# Pico_LED_Matrix_A1.net
KiCad netlist of a schematic drawn in EAGLE
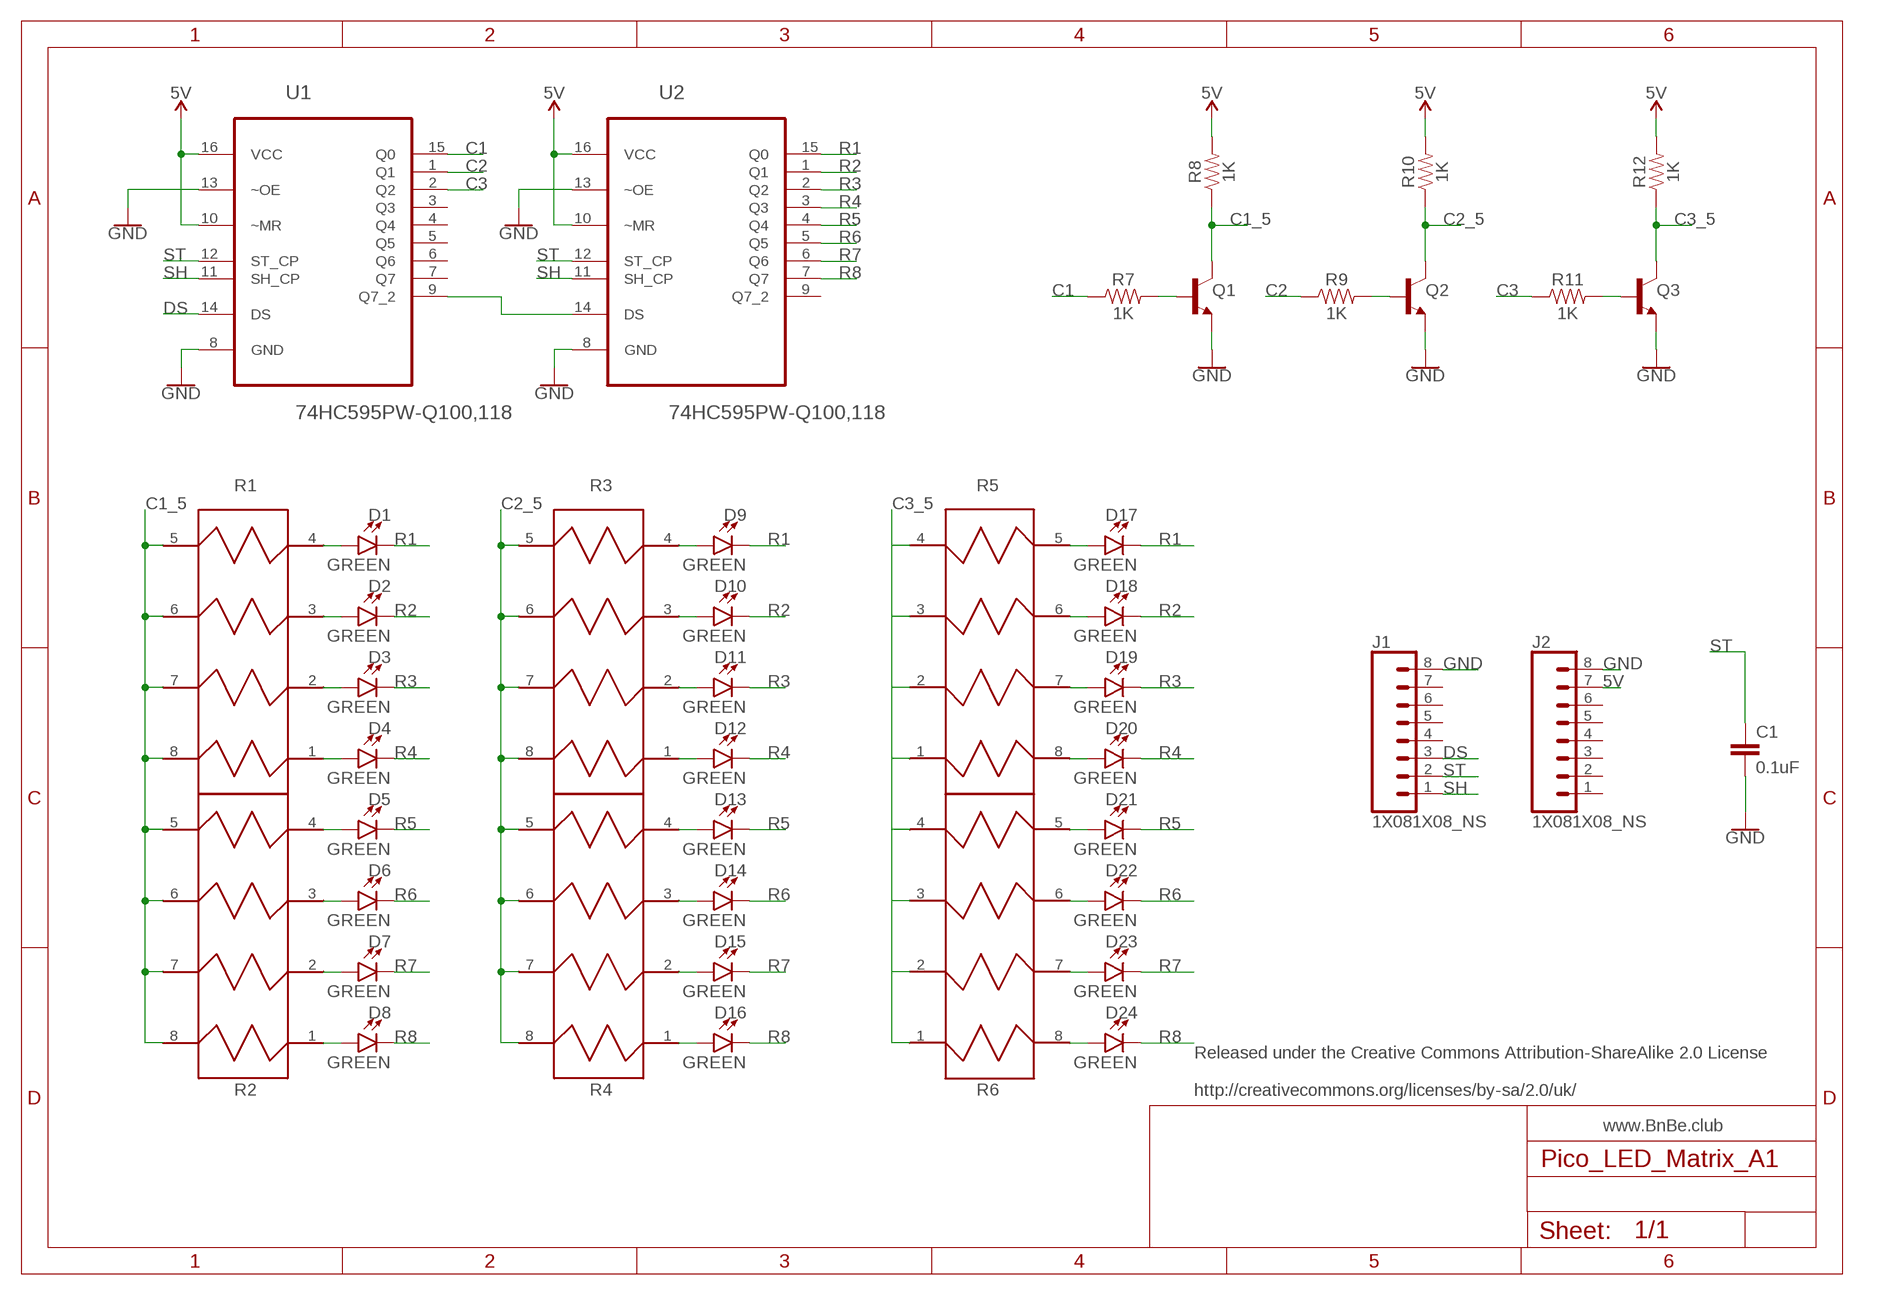
[diagram p0: schematic, sheet 1]

(export (version "E")
  (design (tool "Eeschema 10.0.6"))
  (components
    (comp (ref "C1")
      (value "0.1uF")
      (footprint "eagle-import:0402")
      (libsource (lib "eagle-import") (part "0.1UF-0402-16V-10%"))
    )
    (comp (ref "D1")
      (value "GREEN")
      (footprint "eagle-import:LED-0603")
      (libsource (lib "eagle-import") (part "LED-GREEN0603"))
    )
    (comp (ref "D2")
      (value "GREEN")
      (footprint "eagle-import:LED-0603")
      (libsource (lib "eagle-import") (part "LED-GREEN0603"))
    )
    (comp (ref "D3")
      (value "GREEN")
      (footprint "eagle-import:LED-0603")
      (libsource (lib "eagle-import") (part "LED-GREEN0603"))
    )
    (comp (ref "D4")
      (value "GREEN")
      (footprint "eagle-import:LED-0603")
      (libsource (lib "eagle-import") (part "LED-GREEN0603"))
    )
    (comp (ref "D5")
      (value "GREEN")
      (footprint "eagle-import:LED-0603")
      (libsource (lib "eagle-import") (part "LED-GREEN0603"))
    )
    (comp (ref "D6")
      (value "GREEN")
      (footprint "eagle-import:LED-0603")
      (libsource (lib "eagle-import") (part "LED-GREEN0603"))
    )
    (comp (ref "D7")
      (value "GREEN")
      (footprint "eagle-import:LED-0603")
      (libsource (lib "eagle-import") (part "LED-GREEN0603"))
    )
    (comp (ref "D8")
      (value "GREEN")
      (footprint "eagle-import:LED-0603")
      (libsource (lib "eagle-import") (part "LED-GREEN0603"))
    )
    (comp (ref "D9")
      (value "GREEN")
      (footprint "eagle-import:LED-0603")
      (libsource (lib "eagle-import") (part "LED-GREEN0603"))
    )
    (comp (ref "D10")
      (value "GREEN")
      (footprint "eagle-import:LED-0603")
      (libsource (lib "eagle-import") (part "LED-GREEN0603"))
    )
    (comp (ref "D11")
      (value "GREEN")
      (footprint "eagle-import:LED-0603")
      (libsource (lib "eagle-import") (part "LED-GREEN0603"))
    )
    (comp (ref "D12")
      (value "GREEN")
      (footprint "eagle-import:LED-0603")
      (libsource (lib "eagle-import") (part "LED-GREEN0603"))
    )
    (comp (ref "D13")
      (value "GREEN")
      (footprint "eagle-import:LED-0603")
      (libsource (lib "eagle-import") (part "LED-GREEN0603"))
    )
    (comp (ref "D14")
      (value "GREEN")
      (footprint "eagle-import:LED-0603")
      (libsource (lib "eagle-import") (part "LED-GREEN0603"))
    )
    (comp (ref "D15")
      (value "GREEN")
      (footprint "eagle-import:LED-0603")
      (libsource (lib "eagle-import") (part "LED-GREEN0603"))
    )
    (comp (ref "D16")
      (value "GREEN")
      (footprint "eagle-import:LED-0603")
      (libsource (lib "eagle-import") (part "LED-GREEN0603"))
    )
    (comp (ref "D17")
      (value "GREEN")
      (footprint "eagle-import:LED-0603")
      (libsource (lib "eagle-import") (part "LED-GREEN0603"))
    )
    (comp (ref "D18")
      (value "GREEN")
      (footprint "eagle-import:LED-0603")
      (libsource (lib "eagle-import") (part "LED-GREEN0603"))
    )
    (comp (ref "D19")
      (value "GREEN")
      (footprint "eagle-import:LED-0603")
      (libsource (lib "eagle-import") (part "LED-GREEN0603"))
    )
    (comp (ref "D20")
      (value "GREEN")
      (footprint "eagle-import:LED-0603")
      (libsource (lib "eagle-import") (part "LED-GREEN0603"))
    )
    (comp (ref "D21")
      (value "GREEN")
      (footprint "eagle-import:LED-0603")
      (libsource (lib "eagle-import") (part "LED-GREEN0603"))
    )
    (comp (ref "D22")
      (value "GREEN")
      (footprint "eagle-import:LED-0603")
      (libsource (lib "eagle-import") (part "LED-GREEN0603"))
    )
    (comp (ref "D23")
      (value "GREEN")
      (footprint "eagle-import:LED-0603")
      (libsource (lib "eagle-import") (part "LED-GREEN0603"))
    )
    (comp (ref "D24")
      (value "GREEN")
      (footprint "eagle-import:LED-0603")
      (libsource (lib "eagle-import") (part "LED-GREEN0603"))
    )
    (comp (ref "J1")
      (value "1X081X08_NS")
      (footprint "eagle-import:1X08_NS")
      (libsource (lib "eagle-import") (part "1X081X08_NS"))
    )
    (comp (ref "J2")
      (value "1X081X08_NS")
      (footprint "eagle-import:1X08_NS")
      (libsource (lib "eagle-import") (part "1X081X08_NS"))
    )
    (comp (ref "Q1")
      (value "TRANS_NPN-MMBT2222AL")
      (footprint "eagle-import:SOT23-3")
      (libsource (lib "eagle-import") (part "TRANS_NPN-MMBT2222AL"))
    )
    (comp (ref "Q2")
      (value "TRANS_NPN-MMBT2222AL")
      (footprint "eagle-import:SOT23-3")
      (libsource (lib "eagle-import") (part "TRANS_NPN-MMBT2222AL"))
    )
    (comp (ref "Q3")
      (value "TRANS_NPN-MMBT2222AL")
      (footprint "eagle-import:SOT23-3")
      (libsource (lib "eagle-import") (part "TRANS_NPN-MMBT2222AL"))
    )
    (comp (ref "R1")
      (value "EXBN8V220JX")
      (footprint "eagle-import:RESCAV50P200X100X55-8N")
      (fields (field (name "MF") "Panasonic Electronic") (field (name "MP") "EXB-N8V220JX"))
      (libsource (lib "eagle-import") (part "EXBN8V220JX"))
    )
    (comp (ref "R2")
      (value "EXBN8V220JX")
      (footprint "eagle-import:RESCAV50P200X100X55-8N")
      (fields (field (name "MF") "Panasonic Electronic") (field (name "MP") "EXB-N8V220JX"))
      (libsource (lib "eagle-import") (part "EXBN8V220JX"))
    )
    (comp (ref "R3")
      (value "EXBN8V220JX")
      (footprint "eagle-import:RESCAV50P200X100X55-8N")
      (fields (field (name "MF") "Panasonic Electronic") (field (name "MP") "EXB-N8V220JX"))
      (libsource (lib "eagle-import") (part "EXBN8V220JX"))
    )
    (comp (ref "R4")
      (value "EXBN8V220JX")
      (footprint "eagle-import:RESCAV50P200X100X55-8N")
      (fields (field (name "MF") "Panasonic Electronic") (field (name "MP") "EXB-N8V220JX"))
      (libsource (lib "eagle-import") (part "EXBN8V220JX"))
    )
    (comp (ref "R5")
      (value "EXBN8V220JX")
      (footprint "eagle-import:RESCAV50P200X100X55-8N")
      (fields (field (name "MF") "Panasonic Electronic") (field (name "MP") "EXB-N8V220JX"))
      (libsource (lib "eagle-import") (part "EXBN8V220JX"))
    )
    (comp (ref "R6")
      (value "EXBN8V220JX")
      (footprint "eagle-import:RESCAV50P200X100X55-8N")
      (fields (field (name "MF") "Panasonic Electronic") (field (name "MP") "EXB-N8V220JX"))
      (libsource (lib "eagle-import") (part "EXBN8V220JX"))
    )
    (comp (ref "R7")
      (value "1K")
      (footprint "eagle-import:0402")
      (libsource (lib "eagle-import") (part "RESISTOR0402"))
    )
    (comp (ref "R8")
      (value "1K")
      (footprint "eagle-import:0402")
      (libsource (lib "eagle-import") (part "RESISTOR0402"))
    )
    (comp (ref "R9")
      (value "1K")
      (footprint "eagle-import:0402")
      (libsource (lib "eagle-import") (part "RESISTOR0402"))
    )
    (comp (ref "R10")
      (value "1K")
      (footprint "eagle-import:0402")
      (libsource (lib "eagle-import") (part "RESISTOR0402"))
    )
    (comp (ref "R11")
      (value "1K")
      (footprint "eagle-import:0402")
      (libsource (lib "eagle-import") (part "RESISTOR0402"))
    )
    (comp (ref "R12")
      (value "1K")
      (footprint "eagle-import:0402")
      (libsource (lib "eagle-import") (part "RESISTOR0402"))
    )
    (comp (ref "U1")
      (value "74HC595PW-Q100,118")
      (footprint "eagle-import:SOP65P640X110-16N")
      (fields (field (name "MF") "Nexperia"))
      (libsource (lib "eagle-import") (part "74HC595PW-Q100,118"))
    )
    (comp (ref "U2")
      (value "74HC595PW-Q100,118")
      (footprint "eagle-import:SOP65P640X110-16N")
      (fields (field (name "MF") "Nexperia"))
      (libsource (lib "eagle-import") (part "74HC595PW-Q100,118"))
    )
  )
  (nets
    (net (code "1") (name "/C1") (class "Default")
      (node (ref "R7") (pin "1") (pinfunction "1_1") (pintype "passive"))
      (node (ref "U1") (pin "15") (pinfunction "Q0_15") (pintype "output"))
    )
    (net (code "2") (name "/C1_5") (class "Default")
      (node (ref "Q1") (pin "3") (pinfunction "C_3") (pintype "passive"))
      (node (ref "R1") (pin "5") (pinfunction "5_5") (pintype "passive"))
      (node (ref "R1") (pin "6") (pinfunction "6_6") (pintype "passive"))
      (node (ref "R1") (pin "7") (pinfunction "7_7") (pintype "passive"))
      (node (ref "R1") (pin "8") (pinfunction "8_8") (pintype "passive"))
      (node (ref "R2") (pin "5") (pinfunction "5_5") (pintype "passive"))
      (node (ref "R2") (pin "6") (pinfunction "6_6") (pintype "passive"))
      (node (ref "R2") (pin "7") (pinfunction "7_7") (pintype "passive"))
      (node (ref "R2") (pin "8") (pinfunction "8_8") (pintype "passive"))
      (node (ref "R8") (pin "1") (pinfunction "1_1") (pintype "passive"))
    )
    (net (code "3") (name "/C2") (class "Default")
      (node (ref "R9") (pin "1") (pinfunction "1_1") (pintype "passive"))
      (node (ref "U1") (pin "1") (pinfunction "Q1_1") (pintype "output"))
    )
    (net (code "4") (name "/C2_5") (class "Default")
      (node (ref "Q2") (pin "3") (pinfunction "C_3") (pintype "passive"))
      (node (ref "R10") (pin "1") (pinfunction "1_1") (pintype "passive"))
      (node (ref "R3") (pin "5") (pinfunction "5_5") (pintype "passive"))
      (node (ref "R3") (pin "6") (pinfunction "6_6") (pintype "passive"))
      (node (ref "R3") (pin "7") (pinfunction "7_7") (pintype "passive"))
      (node (ref "R3") (pin "8") (pinfunction "8_8") (pintype "passive"))
      (node (ref "R4") (pin "5") (pinfunction "5_5") (pintype "passive"))
      (node (ref "R4") (pin "6") (pinfunction "6_6") (pintype "passive"))
      (node (ref "R4") (pin "7") (pinfunction "7_7") (pintype "passive"))
      (node (ref "R4") (pin "8") (pinfunction "8_8") (pintype "passive"))
    )
    (net (code "5") (name "/C3") (class "Default")
      (node (ref "R11") (pin "1") (pinfunction "1_1") (pintype "passive"))
      (node (ref "U1") (pin "2") (pinfunction "Q2_2") (pintype "output"))
    )
    (net (code "6") (name "/C3_5") (class "Default")
      (node (ref "Q3") (pin "3") (pinfunction "C_3") (pintype "passive"))
      (node (ref "R12") (pin "1") (pinfunction "1_1") (pintype "passive"))
      (node (ref "R5") (pin "1") (pinfunction "1_1") (pintype "passive"))
      (node (ref "R5") (pin "2") (pinfunction "2_2") (pintype "passive"))
      (node (ref "R5") (pin "3") (pinfunction "3_3") (pintype "passive"))
      (node (ref "R5") (pin "4") (pinfunction "4_4") (pintype "passive"))
      (node (ref "R6") (pin "1") (pinfunction "1_1") (pintype "passive"))
      (node (ref "R6") (pin "2") (pinfunction "2_2") (pintype "passive"))
      (node (ref "R6") (pin "3") (pinfunction "3_3") (pintype "passive"))
      (node (ref "R6") (pin "4") (pinfunction "4_4") (pintype "passive"))
    )
    (net (code "7") (name "/DS") (class "Default")
      (node (ref "J1") (pin "3") (pinfunction "3_3") (pintype "passive"))
      (node (ref "U1") (pin "14") (pinfunction "DS_14") (pintype "input"))
    )
    (net (code "8") (name "/R1") (class "Default")
      (node (ref "D1") (pin "C") (pinfunction "C_C") (pintype "passive"))
      (node (ref "D17") (pin "C") (pinfunction "C_C") (pintype "passive"))
      (node (ref "D9") (pin "C") (pinfunction "C_C") (pintype "passive"))
      (node (ref "U2") (pin "15") (pinfunction "Q0_15") (pintype "output"))
    )
    (net (code "9") (name "/R2") (class "Default")
      (node (ref "D10") (pin "C") (pinfunction "C_C") (pintype "passive"))
      (node (ref "D18") (pin "C") (pinfunction "C_C") (pintype "passive"))
      (node (ref "D2") (pin "C") (pinfunction "C_C") (pintype "passive"))
      (node (ref "U2") (pin "1") (pinfunction "Q1_1") (pintype "output"))
    )
    (net (code "10") (name "/R3") (class "Default")
      (node (ref "D11") (pin "C") (pinfunction "C_C") (pintype "passive"))
      (node (ref "D19") (pin "C") (pinfunction "C_C") (pintype "passive"))
      (node (ref "D3") (pin "C") (pinfunction "C_C") (pintype "passive"))
      (node (ref "U2") (pin "2") (pinfunction "Q2_2") (pintype "output"))
    )
    (net (code "11") (name "/R4") (class "Default")
      (node (ref "D12") (pin "C") (pinfunction "C_C") (pintype "passive"))
      (node (ref "D20") (pin "C") (pinfunction "C_C") (pintype "passive"))
      (node (ref "D4") (pin "C") (pinfunction "C_C") (pintype "passive"))
      (node (ref "U2") (pin "3") (pinfunction "Q3_3") (pintype "output"))
    )
    (net (code "12") (name "/R5") (class "Default")
      (node (ref "D13") (pin "C") (pinfunction "C_C") (pintype "passive"))
      (node (ref "D21") (pin "C") (pinfunction "C_C") (pintype "passive"))
      (node (ref "D5") (pin "C") (pinfunction "C_C") (pintype "passive"))
      (node (ref "U2") (pin "4") (pinfunction "Q4_4") (pintype "output"))
    )
    (net (code "13") (name "/R6") (class "Default")
      (node (ref "D14") (pin "C") (pinfunction "C_C") (pintype "passive"))
      (node (ref "D22") (pin "C") (pinfunction "C_C") (pintype "passive"))
      (node (ref "D6") (pin "C") (pinfunction "C_C") (pintype "passive"))
      (node (ref "U2") (pin "5") (pinfunction "Q5_5") (pintype "output"))
    )
    (net (code "14") (name "/R7") (class "Default")
      (node (ref "D15") (pin "C") (pinfunction "C_C") (pintype "passive"))
      (node (ref "D23") (pin "C") (pinfunction "C_C") (pintype "passive"))
      (node (ref "D7") (pin "C") (pinfunction "C_C") (pintype "passive"))
      (node (ref "U2") (pin "6") (pinfunction "Q6_6") (pintype "output"))
    )
    (net (code "15") (name "/R8") (class "Default")
      (node (ref "D16") (pin "C") (pinfunction "C_C") (pintype "passive"))
      (node (ref "D24") (pin "C") (pinfunction "C_C") (pintype "passive"))
      (node (ref "D8") (pin "C") (pinfunction "C_C") (pintype "passive"))
      (node (ref "U2") (pin "7") (pinfunction "Q7_7") (pintype "output"))
    )
    (net (code "16") (name "/SH") (class "Default")
      (node (ref "J1") (pin "1") (pinfunction "1_1") (pintype "passive"))
      (node (ref "U1") (pin "11") (pinfunction "SH_CP_11") (pintype "input"))
      (node (ref "U2") (pin "11") (pinfunction "SH_CP_11") (pintype "input"))
    )
    (net (code "17") (name "/ST") (class "Default")
      (node (ref "C1") (pin "1") (pinfunction "1_1") (pintype "passive"))
      (node (ref "J1") (pin "2") (pinfunction "2_2") (pintype "passive"))
      (node (ref "U1") (pin "12") (pinfunction "ST_CP_12") (pintype "input"))
      (node (ref "U2") (pin "12") (pinfunction "ST_CP_12") (pintype "input"))
    )
    (net (code "18") (name "5V") (class "Default")
      (node (ref "J2") (pin "7") (pinfunction "7_7") (pintype "passive"))
      (node (ref "R10") (pin "2") (pinfunction "2_2") (pintype "passive"))
      (node (ref "R12") (pin "2") (pinfunction "2_2") (pintype "passive"))
      (node (ref "R8") (pin "2") (pinfunction "2_2") (pintype "passive"))
      (node (ref "U1") (pin "10") (pinfunction "~{MR}_10") (pintype "input"))
      (node (ref "U1") (pin "16") (pinfunction "VCC_16") (pintype "power_in"))
      (node (ref "U2") (pin "10") (pinfunction "~{MR}_10") (pintype "input"))
      (node (ref "U2") (pin "16") (pinfunction "VCC_16") (pintype "power_in"))
    )
    (net (code "19") (name "GND") (class "Default")
      (node (ref "C1") (pin "2") (pinfunction "2_2") (pintype "passive"))
      (node (ref "J1") (pin "8") (pinfunction "8_8") (pintype "passive"))
      (node (ref "J2") (pin "8") (pinfunction "8_8") (pintype "passive"))
      (node (ref "Q1") (pin "2") (pinfunction "E_2") (pintype "passive"))
      (node (ref "Q2") (pin "2") (pinfunction "E_2") (pintype "passive"))
      (node (ref "Q3") (pin "2") (pinfunction "E_2") (pintype "passive"))
      (node (ref "U1") (pin "13") (pinfunction "~{OE}_13") (pintype "input"))
      (node (ref "U1") (pin "8") (pinfunction "GND_8") (pintype "passive"))
      (node (ref "U2") (pin "13") (pinfunction "~{OE}_13") (pintype "input"))
      (node (ref "U2") (pin "8") (pinfunction "GND_8") (pintype "passive"))
    )
    (net (code "20") (name "Net-(D1-PadA)") (class "Default")
      (node (ref "D1") (pin "A") (pinfunction "A_A") (pintype "passive"))
      (node (ref "R1") (pin "4") (pinfunction "4_4") (pintype "passive"))
    )
    (net (code "21") (name "Net-(D2-PadA)") (class "Default")
      (node (ref "D2") (pin "A") (pinfunction "A_A") (pintype "passive"))
      (node (ref "R1") (pin "3") (pinfunction "3_3") (pintype "passive"))
    )
    (net (code "22") (name "Net-(D3-PadA)") (class "Default")
      (node (ref "D3") (pin "A") (pinfunction "A_A") (pintype "passive"))
      (node (ref "R1") (pin "2") (pinfunction "2_2") (pintype "passive"))
    )
    (net (code "23") (name "Net-(D4-PadA)") (class "Default")
      (node (ref "D4") (pin "A") (pinfunction "A_A") (pintype "passive"))
      (node (ref "R1") (pin "1") (pinfunction "1_1") (pintype "passive"))
    )
    (net (code "24") (name "Net-(D5-PadA)") (class "Default")
      (node (ref "D5") (pin "A") (pinfunction "A_A") (pintype "passive"))
      (node (ref "R2") (pin "4") (pinfunction "4_4") (pintype "passive"))
    )
    (net (code "25") (name "Net-(D6-PadA)") (class "Default")
      (node (ref "D6") (pin "A") (pinfunction "A_A") (pintype "passive"))
      (node (ref "R2") (pin "3") (pinfunction "3_3") (pintype "passive"))
    )
    (net (code "26") (name "Net-(D7-PadA)") (class "Default")
      (node (ref "D7") (pin "A") (pinfunction "A_A") (pintype "passive"))
      (node (ref "R2") (pin "2") (pinfunction "2_2") (pintype "passive"))
    )
    (net (code "27") (name "Net-(D8-PadA)") (class "Default")
      (node (ref "D8") (pin "A") (pinfunction "A_A") (pintype "passive"))
      (node (ref "R2") (pin "1") (pinfunction "1_1") (pintype "passive"))
    )
    (net (code "28") (name "Net-(D9-PadA)") (class "Default")
      (node (ref "D9") (pin "A") (pinfunction "A_A") (pintype "passive"))
      (node (ref "R3") (pin "4") (pinfunction "4_4") (pintype "passive"))
    )
    (net (code "29") (name "Net-(D10-PadA)") (class "Default")
      (node (ref "D10") (pin "A") (pinfunction "A_A") (pintype "passive"))
      (node (ref "R3") (pin "3") (pinfunction "3_3") (pintype "passive"))
    )
    (net (code "30") (name "Net-(D11-PadA)") (class "Default")
      (node (ref "D11") (pin "A") (pinfunction "A_A") (pintype "passive"))
      (node (ref "R3") (pin "2") (pinfunction "2_2") (pintype "passive"))
    )
    (net (code "31") (name "Net-(D12-PadA)") (class "Default")
      (node (ref "D12") (pin "A") (pinfunction "A_A") (pintype "passive"))
      (node (ref "R3") (pin "1") (pinfunction "1_1") (pintype "passive"))
    )
    (net (code "32") (name "Net-(D13-PadA)") (class "Default")
      (node (ref "D13") (pin "A") (pinfunction "A_A") (pintype "passive"))
      (node (ref "R4") (pin "4") (pinfunction "4_4") (pintype "passive"))
    )
    (net (code "33") (name "Net-(D14-PadA)") (class "Default")
      (node (ref "D14") (pin "A") (pinfunction "A_A") (pintype "passive"))
      (node (ref "R4") (pin "3") (pinfunction "3_3") (pintype "passive"))
    )
    (net (code "34") (name "Net-(D15-PadA)") (class "Default")
      (node (ref "D15") (pin "A") (pinfunction "A_A") (pintype "passive"))
      (node (ref "R4") (pin "2") (pinfunction "2_2") (pintype "passive"))
    )
    (net (code "35") (name "Net-(D16-PadA)") (class "Default")
      (node (ref "D16") (pin "A") (pinfunction "A_A") (pintype "passive"))
      (node (ref "R4") (pin "1") (pinfunction "1_1") (pintype "passive"))
    )
    (net (code "36") (name "Net-(D17-PadA)") (class "Default")
      (node (ref "D17") (pin "A") (pinfunction "A_A") (pintype "passive"))
      (node (ref "R5") (pin "5") (pinfunction "5_5") (pintype "passive"))
    )
    (net (code "37") (name "Net-(D18-PadA)") (class "Default")
      (node (ref "D18") (pin "A") (pinfunction "A_A") (pintype "passive"))
      (node (ref "R5") (pin "6") (pinfunction "6_6") (pintype "passive"))
    )
    (net (code "38") (name "Net-(D19-PadA)") (class "Default")
      (node (ref "D19") (pin "A") (pinfunction "A_A") (pintype "passive"))
      (node (ref "R5") (pin "7") (pinfunction "7_7") (pintype "passive"))
    )
    (net (code "39") (name "Net-(D20-PadA)") (class "Default")
      (node (ref "D20") (pin "A") (pinfunction "A_A") (pintype "passive"))
      (node (ref "R5") (pin "8") (pinfunction "8_8") (pintype "passive"))
    )
    (net (code "40") (name "Net-(D21-PadA)") (class "Default")
      (node (ref "D21") (pin "A") (pinfunction "A_A") (pintype "passive"))
      (node (ref "R6") (pin "5") (pinfunction "5_5") (pintype "passive"))
    )
    (net (code "41") (name "Net-(D22-PadA)") (class "Default")
      (node (ref "D22") (pin "A") (pinfunction "A_A") (pintype "passive"))
      (node (ref "R6") (pin "6") (pinfunction "6_6") (pintype "passive"))
    )
    (net (code "42") (name "Net-(D23-PadA)") (class "Default")
      (node (ref "D23") (pin "A") (pinfunction "A_A") (pintype "passive"))
      (node (ref "R6") (pin "7") (pinfunction "7_7") (pintype "passive"))
    )
    (net (code "43") (name "Net-(D24-PadA)") (class "Default")
      (node (ref "D24") (pin "A") (pinfunction "A_A") (pintype "passive"))
      (node (ref "R6") (pin "8") (pinfunction "8_8") (pintype "passive"))
    )
    (net (code "44") (name "Net-(Q1-B)") (class "Default")
      (node (ref "Q1") (pin "1") (pinfunction "B_1") (pintype "passive"))
      (node (ref "R7") (pin "2") (pinfunction "2_2") (pintype "passive"))
    )
    (net (code "45") (name "Net-(Q2-B)") (class "Default")
      (node (ref "Q2") (pin "1") (pinfunction "B_1") (pintype "passive"))
      (node (ref "R9") (pin "2") (pinfunction "2_2") (pintype "passive"))
    )
    (net (code "46") (name "Net-(Q3-B)") (class "Default")
      (node (ref "Q3") (pin "1") (pinfunction "B_1") (pintype "passive"))
      (node (ref "R11") (pin "2") (pinfunction "2_2") (pintype "passive"))
    )
    (net (code "47") (name "Net-(U1-Q7_2)") (class "Default")
      (node (ref "U1") (pin "9") (pinfunction "Q7_2_9") (pintype "output"))
      (node (ref "U2") (pin "14") (pinfunction "DS_14") (pintype "input"))
    )
    (net (code "48") (name "unconnected-(J1-Pad4)") (class "Default")
      (node (ref "J1") (pin "4") (pinfunction "4_4") (pintype "passive"))
    )
    (net (code "49") (name "unconnected-(J1-Pad5)") (class "Default")
      (node (ref "J1") (pin "5") (pinfunction "5_5") (pintype "passive"))
    )
    (net (code "50") (name "unconnected-(J1-Pad6)") (class "Default")
      (node (ref "J1") (pin "6") (pinfunction "6_6") (pintype "passive"))
    )
    (net (code "51") (name "unconnected-(J1-Pad7)") (class "Default")
      (node (ref "J1") (pin "7") (pinfunction "7_7") (pintype "passive"))
    )
    (net (code "52") (name "unconnected-(J2-Pad1)") (class "Default")
      (node (ref "J2") (pin "1") (pinfunction "1_1") (pintype "passive"))
    )
    (net (code "53") (name "unconnected-(J2-Pad2)") (class "Default")
      (node (ref "J2") (pin "2") (pinfunction "2_2") (pintype "passive"))
    )
    (net (code "54") (name "unconnected-(J2-Pad3)") (class "Default")
      (node (ref "J2") (pin "3") (pinfunction "3_3") (pintype "passive"))
    )
    (net (code "55") (name "unconnected-(J2-Pad4)") (class "Default")
      (node (ref "J2") (pin "4") (pinfunction "4_4") (pintype "passive"))
    )
    (net (code "56") (name "unconnected-(J2-Pad5)") (class "Default")
      (node (ref "J2") (pin "5") (pinfunction "5_5") (pintype "passive"))
    )
    (net (code "57") (name "unconnected-(J2-Pad6)") (class "Default")
      (node (ref "J2") (pin "6") (pinfunction "6_6") (pintype "passive"))
    )
    (net (code "58") (name "unconnected-(U1-Q3-Pad3)") (class "Default")
      (node (ref "U1") (pin "3") (pinfunction "Q3_3") (pintype "output"))
    )
    (net (code "59") (name "unconnected-(U1-Q4-Pad4)") (class "Default")
      (node (ref "U1") (pin "4") (pinfunction "Q4_4") (pintype "output"))
    )
    (net (code "60") (name "unconnected-(U1-Q5-Pad5)") (class "Default")
      (node (ref "U1") (pin "5") (pinfunction "Q5_5") (pintype "output"))
    )
    (net (code "61") (name "unconnected-(U1-Q6-Pad6)") (class "Default")
      (node (ref "U1") (pin "6") (pinfunction "Q6_6") (pintype "output"))
    )
    (net (code "62") (name "unconnected-(U1-Q7-Pad7)") (class "Default")
      (node (ref "U1") (pin "7") (pinfunction "Q7_7") (pintype "output"))
    )
    (net (code "63") (name "unconnected-(U2-Q7_2-Pad9)") (class "Default")
      (node (ref "U2") (pin "9") (pinfunction "Q7_2_9") (pintype "output"))
    )
  )
)
